# TALON_SRX_v2_0.net
KiCad netlist of a schematic drawn in EAGLE
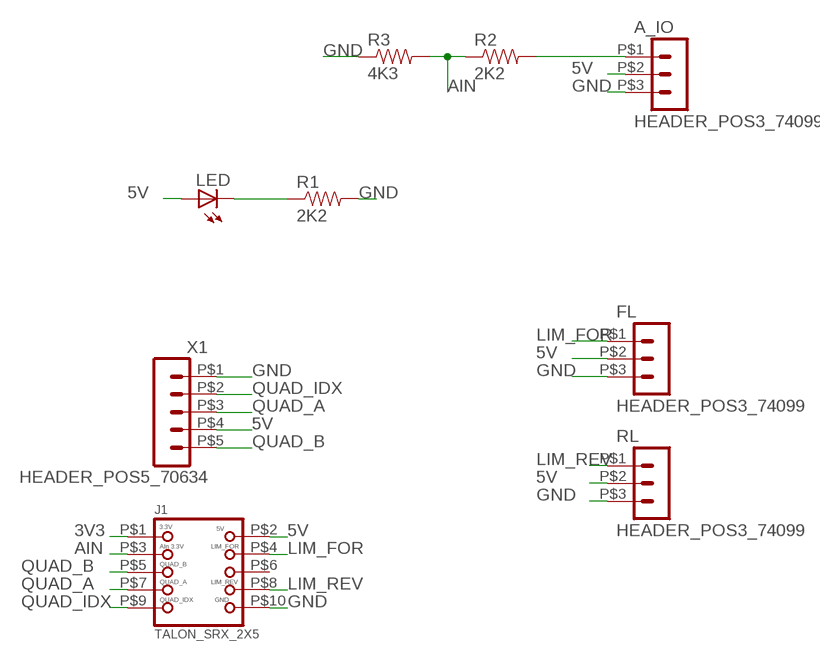
[diagram p0: schematic, sheet 1]

(export (version "E")
  (design (tool "Eeschema 10.0.6"))
  (components
    (comp (ref "A_IO")
      (value "HEADER_POS3_74099")
      (footprint "eagle-import:74099-POS3")
      (libsource (lib "eagle-import") (part "HEADER_POS3_?74099"))
    )
    (comp (ref "FL")
      (value "HEADER_POS3_74099")
      (footprint "eagle-import:74099-POS3")
      (libsource (lib "eagle-import") (part "HEADER_POS3_?74099"))
    )
    (comp (ref "J1")
      (value "TALON_SRX_2X5")
      (footprint "eagle-import:2X5-0.05-HEADER")
      (libsource (lib "eagle-import") (part "TALON_SRX_2X5"))
    )
    (comp (ref "LED")
      (value "LEDSMT1206")
      (footprint "eagle-import:1206")
      (libsource (lib "eagle-import") (part "LEDSMT1206"))
    )
    (comp (ref "R1")
      (value "2K2")
      (footprint "eagle-import:1206")
      (libsource (lib "eagle-import") (part "RESISTOR1206"))
    )
    (comp (ref "R2")
      (value "2K2")
      (footprint "eagle-import:1206")
      (libsource (lib "eagle-import") (part "RESISTOR1206"))
    )
    (comp (ref "R3")
      (value "4K3")
      (footprint "eagle-import:1206")
      (libsource (lib "eagle-import") (part "RESISTOR1206"))
    )
    (comp (ref "RL")
      (value "HEADER_POS3_74099")
      (footprint "eagle-import:74099-POS3")
      (libsource (lib "eagle-import") (part "HEADER_POS3_?74099"))
    )
    (comp (ref "X1")
      (value "HEADER_POS5_70634")
      (footprint "eagle-import:70634-POS5")
      (libsource (lib "eagle-import") (part "HEADER_POS5_?70634"))
    )
  )
  (nets
    (net (code "1") (name "/3V3") (class "Default")
      (node (ref "J1") (pin "P$1") (pinfunction "1_P$1") (pintype "passive"))
    )
    (net (code "2") (name "/5V") (class "Default")
      (node (ref "A_IO") (pin "P$2") (pinfunction "2_P$2") (pintype "passive"))
      (node (ref "FL") (pin "P$2") (pinfunction "2_P$2") (pintype "passive"))
      (node (ref "J1") (pin "P$2") (pinfunction "2_P$2") (pintype "passive"))
      (node (ref "LED") (pin "A") (pinfunction "A_A") (pintype "passive"))
      (node (ref "RL") (pin "P$2") (pinfunction "2_P$2") (pintype "passive"))
      (node (ref "X1") (pin "P$4") (pinfunction "4_P$4") (pintype "passive"))
    )
    (net (code "3") (name "/AIN") (class "Default")
      (node (ref "J1") (pin "P$3") (pinfunction "3_P$3") (pintype "passive"))
      (node (ref "R2") (pin "1") (pinfunction "1_1") (pintype "passive"))
      (node (ref "R3") (pin "2") (pinfunction "2_2") (pintype "passive"))
    )
    (net (code "4") (name "/GND") (class "Default")
      (node (ref "A_IO") (pin "P$3") (pinfunction "3_P$3") (pintype "passive"))
      (node (ref "FL") (pin "P$3") (pinfunction "3_P$3") (pintype "passive"))
      (node (ref "J1") (pin "P$10") (pinfunction "10_P$10") (pintype "passive"))
      (node (ref "R1") (pin "2") (pinfunction "2_2") (pintype "passive"))
      (node (ref "R3") (pin "1") (pinfunction "1_1") (pintype "passive"))
      (node (ref "RL") (pin "P$3") (pinfunction "3_P$3") (pintype "passive"))
      (node (ref "X1") (pin "P$1") (pinfunction "1_P$1") (pintype "passive"))
    )
    (net (code "5") (name "/LIM_FOR") (class "Default")
      (node (ref "FL") (pin "P$1") (pinfunction "1_P$1") (pintype "passive"))
      (node (ref "J1") (pin "P$4") (pinfunction "4_P$4") (pintype "passive"))
    )
    (net (code "6") (name "/LIM_REV") (class "Default")
      (node (ref "J1") (pin "P$8") (pinfunction "8_P$8") (pintype "passive"))
      (node (ref "RL") (pin "P$1") (pinfunction "1_P$1") (pintype "passive"))
    )
    (net (code "7") (name "/QUAD_A") (class "Default")
      (node (ref "J1") (pin "P$7") (pinfunction "7_P$7") (pintype "passive"))
      (node (ref "X1") (pin "P$3") (pinfunction "3_P$3") (pintype "passive"))
    )
    (net (code "8") (name "/QUAD_B") (class "Default")
      (node (ref "J1") (pin "P$5") (pinfunction "5_P$5") (pintype "passive"))
      (node (ref "X1") (pin "P$5") (pinfunction "5_P$5") (pintype "passive"))
    )
    (net (code "9") (name "/QUAD_IDX") (class "Default")
      (node (ref "J1") (pin "P$9") (pinfunction "9_P$9") (pintype "passive"))
      (node (ref "X1") (pin "P$2") (pinfunction "2_P$2") (pintype "passive"))
    )
    (net (code "10") (name "Net-(A_IO-1)") (class "Default")
      (node (ref "A_IO") (pin "P$1") (pinfunction "1_P$1") (pintype "passive"))
      (node (ref "R2") (pin "2") (pinfunction "2_2") (pintype "passive"))
    )
    (net (code "11") (name "Net-(LED-PadC)") (class "Default")
      (node (ref "LED") (pin "C") (pinfunction "C_C") (pintype "passive"))
      (node (ref "R1") (pin "1") (pinfunction "1_1") (pintype "passive"))
    )
    (net (code "12") (name "unconnected-(J1-6-PadP$6)") (class "Default")
      (node (ref "J1") (pin "P$6") (pinfunction "6_P$6") (pintype "passive"))
    )
  )
)
